# CAN.net
KiCad netlist of a schematic drawn in Altium Designer
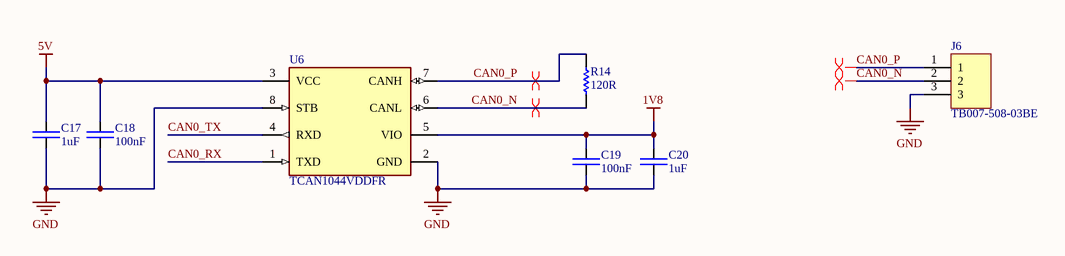
[diagram p0: CAN.SchDoc]

(export (version "E")
  (design (tool "Eeschema 10.0.6"))
  (components
    (comp (ref "C17")
      (value "1uF")
      (footprint "CAP-0805")
      (description "Capacitor chip unpolarized. 0805")
      (libsource (lib "Master") (part "CAP-0805"))
    )
    (comp (ref "C18")
      (value "100nF")
      (footprint "CAP-0603")
      (description "Capacitor chip unpolarized. 0603")
      (libsource (lib "Master") (part "CAP-0603"))
    )
    (comp (ref "C19")
      (value "100nF")
      (footprint "CAP-0603")
      (description "Capacitor chip unpolarized. 0603")
      (libsource (lib "Master") (part "CAP-0603"))
    )
    (comp (ref "C20")
      (value "1uF")
      (footprint "CAP-0805")
      (description "Capacitor chip unpolarized. 0805")
      (libsource (lib "Master") (part "CAP-0805"))
    )
    (comp (ref "J6")
      (value "TB007-508-03BE")
      (footprint "CUI_TB007-508-03BE")
      (description "3 Pos, Screw Type, Horizontal, 5.08 Pitch, 24~12 (AWG), Terminal Block Connector")
      (fields (field (name "MF") "Same Sky"))
      (libsource (lib "Master") (part "TB007-508-03BE"))
    )
    (comp (ref "R14")
      (value "120R")
      (footprint "RES-0603")
      (description "Resistor chip. 0603")
      (libsource (lib "Master") (part "RES-0603"))
    )
    (comp (ref "U6")
      (value "TCAN1044VDDFR")
      (footprint "FP-DDF0008A-MFG")
      (description "IC TRANSCEIVER FULL 1/1 SOT23-8")
      (libsource (lib "Altium Content Vault") (part "07a38a3f496b147e1c88e0a0638d013"))
    )
  )
  (nets
    (net (code "1") (name "/CAN0_N") (class "Default")
      (node (ref "J6") (pin "2") (pinfunction "2_2") (pintype "passive"))
      (node (ref "R14") (pin "1") (pintype "passive"))
      (node (ref "U6") (pin "6") (pinfunction "CANL_6") (pintype "bidirectional"))
    )
    (net (code "2") (name "/CAN0_P") (class "Default")
      (node (ref "J6") (pin "1") (pinfunction "1_1") (pintype "passive"))
      (node (ref "R14") (pin "2") (pintype "passive"))
      (node (ref "U6") (pin "7") (pinfunction "CANH_7") (pintype "bidirectional"))
    )
    (net (code "3") (name "/CAN0_RX") (class "Default")
      (node (ref "U6") (pin "1") (pinfunction "TXD_1") (pintype "input"))
    )
    (net (code "4") (name "/CAN0_TX") (class "Default")
      (node (ref "U6") (pin "4") (pinfunction "RXD_4") (pintype "output"))
    )
    (net (code "5") (name "1V8") (class "Default")
      (node (ref "C19") (pin "2") (pintype "passive"))
      (node (ref "C20") (pin "2") (pintype "passive"))
      (node (ref "U6") (pin "5") (pinfunction "VIO_5") (pintype "power_in"))
    )
    (net (code "6") (name "5V") (class "Default")
      (node (ref "C17") (pin "2") (pintype "passive"))
      (node (ref "C18") (pin "2") (pintype "passive"))
      (node (ref "U6") (pin "3") (pinfunction "VCC_3") (pintype "power_in"))
    )
    (net (code "7") (name "GND") (class "Default")
      (node (ref "C17") (pin "1") (pintype "passive"))
      (node (ref "C18") (pin "1") (pintype "passive"))
      (node (ref "C19") (pin "1") (pintype "passive"))
      (node (ref "C20") (pin "1") (pintype "passive"))
      (node (ref "J6") (pin "3") (pinfunction "3_3") (pintype "passive"))
      (node (ref "U6") (pin "2") (pinfunction "GND_2") (pintype "power_in"))
      (node (ref "U6") (pin "8") (pinfunction "STB_8") (pintype "input"))
    )
  )
)
